# amiga-akab.net
KiCad netlist of a schematic drawn in EAGLE
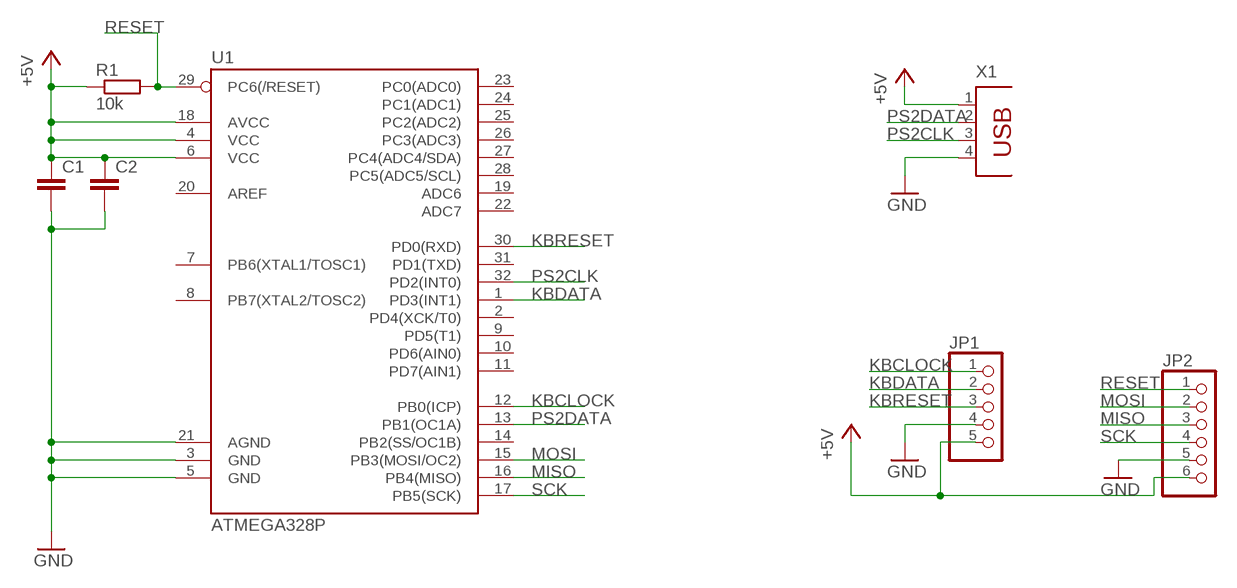
[diagram p0: schematic, sheet 1]

(export (version "E")
  (design (tool "Eeschema 10.0.6"))
  (components
    (comp (ref "C1")
      (value "C-EUC0603")
      (footprint "eagle-import:C0603")
      (libsource (lib "eagle-import") (part "C-EUC0603"))
    )
    (comp (ref "C2")
      (value "C-EUC0603")
      (footprint "eagle-import:C0603")
      (libsource (lib "eagle-import") (part "C-EUC0603"))
    )
    (comp (ref "JP1")
      (value "HEADER-1X5ROUND")
      (footprint "eagle-import:1X05_ROUND")
      (libsource (lib "eagle-import") (part "HEADER-1X5ROUND"))
    )
    (comp (ref "JP2")
      (value "HEADER-1X6ROUND")
      (footprint "eagle-import:1X06_ROUND")
      (libsource (lib "eagle-import") (part "HEADER-1X6ROUND"))
    )
    (comp (ref "R1")
      (value "10k")
      (footprint "eagle-import:R0603")
      (libsource (lib "eagle-import") (part "R-EU_R0603"))
    )
    (comp (ref "U1")
      (value "ATMEGA328P")
      (footprint "eagle-import:TQFP32-08")
      (libsource (lib "eagle-import") (part "ATMEGA328P_TQFP"))
    )
    (comp (ref "X1")
      (value "PN87520")
      (footprint "eagle-import:PN87520")
      (libsource (lib "eagle-import") (part "PN87520"))
    )
  )
  (nets
    (net (code "1") (name "+5V") (class "Default")
      (node (ref "C1") (pin "1") (pinfunction "1_1") (pintype "passive"))
      (node (ref "C2") (pin "1") (pinfunction "1_1") (pintype "passive"))
      (node (ref "JP1") (pin "5") (pinfunction "5_5") (pintype "passive"))
      (node (ref "JP2") (pin "6") (pinfunction "6_6") (pintype "passive"))
      (node (ref "R1") (pin "1") (pinfunction "1_1") (pintype "passive"))
      (node (ref "U1") (pin "18") (pinfunction "AVCC_18") (pintype "bidirectional"))
      (node (ref "U1") (pin "4") (pinfunction "VCC_4") (pintype "bidirectional"))
      (node (ref "U1") (pin "6") (pinfunction "VCC_6") (pintype "bidirectional"))
      (node (ref "X1") (pin "1") (pinfunction "1_1") (pintype "passive"))
    )
    (net (code "2") (name "/KBCLOCK") (class "Default")
      (node (ref "JP1") (pin "1") (pinfunction "1_1") (pintype "passive"))
      (node (ref "U1") (pin "12") (pinfunction "PB0(ICP)_12") (pintype "bidirectional"))
    )
    (net (code "3") (name "/KBDATA") (class "Default")
      (node (ref "JP1") (pin "2") (pinfunction "2_2") (pintype "passive"))
      (node (ref "U1") (pin "1") (pinfunction "PD3(INT1)_1") (pintype "bidirectional"))
    )
    (net (code "4") (name "/KBRESET") (class "Default")
      (node (ref "JP1") (pin "3") (pinfunction "3_3") (pintype "passive"))
      (node (ref "U1") (pin "30") (pinfunction "PD0(RXD)_30") (pintype "bidirectional"))
    )
    (net (code "5") (name "/MISO") (class "Default")
      (node (ref "JP2") (pin "3") (pinfunction "3_3") (pintype "passive"))
      (node (ref "U1") (pin "16") (pinfunction "PB4(MISO)_16") (pintype "bidirectional"))
    )
    (net (code "6") (name "/MOSI") (class "Default")
      (node (ref "JP2") (pin "2") (pinfunction "2_2") (pintype "passive"))
      (node (ref "U1") (pin "15") (pinfunction "PB3(MOSI/OC2)_15") (pintype "bidirectional"))
    )
    (net (code "7") (name "/PS2CLK") (class "Default")
      (node (ref "U1") (pin "32") (pinfunction "PD2(INT0)_32") (pintype "bidirectional"))
      (node (ref "X1") (pin "3") (pinfunction "3_3") (pintype "passive"))
    )
    (net (code "8") (name "/PS2DATA") (class "Default")
      (node (ref "U1") (pin "13") (pinfunction "PB1(OC1A)_13") (pintype "bidirectional"))
      (node (ref "X1") (pin "2") (pinfunction "2_2") (pintype "passive"))
    )
    (net (code "9") (name "/RESET") (class "Default")
      (node (ref "JP2") (pin "1") (pinfunction "1_1") (pintype "passive"))
      (node (ref "R1") (pin "2") (pinfunction "2_2") (pintype "passive"))
      (node (ref "U1") (pin "29") (pinfunction "PC6(/RESET)_29") (pintype "bidirectional"))
    )
    (net (code "10") (name "/SCK") (class "Default")
      (node (ref "JP2") (pin "4") (pinfunction "4_4") (pintype "passive"))
      (node (ref "U1") (pin "17") (pinfunction "PB5(SCK)_17") (pintype "bidirectional"))
    )
    (net (code "11") (name "GND") (class "Default")
      (node (ref "C1") (pin "2") (pinfunction "2_2") (pintype "passive"))
      (node (ref "C2") (pin "2") (pinfunction "2_2") (pintype "passive"))
      (node (ref "JP1") (pin "4") (pinfunction "4_4") (pintype "passive"))
      (node (ref "JP2") (pin "5") (pinfunction "5_5") (pintype "passive"))
      (node (ref "U1") (pin "21") (pinfunction "AGND_21") (pintype "bidirectional"))
      (node (ref "U1") (pin "3") (pinfunction "GND_3") (pintype "bidirectional"))
      (node (ref "U1") (pin "5") (pinfunction "GND_5") (pintype "bidirectional"))
      (node (ref "X1") (pin "4") (pinfunction "4_4") (pintype "passive"))
    )
    (net (code "12") (name "unconnected-(U1-ADC6-Pad19)") (class "Default")
      (node (ref "U1") (pin "19") (pinfunction "ADC6_19") (pintype "bidirectional"))
    )
    (net (code "13") (name "unconnected-(U1-ADC7-Pad22)") (class "Default")
      (node (ref "U1") (pin "22") (pinfunction "ADC7_22") (pintype "bidirectional"))
    )
    (net (code "14") (name "unconnected-(U1-AREF-Pad20)") (class "Default")
      (node (ref "U1") (pin "20") (pinfunction "AREF_20") (pintype "bidirectional"))
    )
    (net (code "15") (name "unconnected-(U1-PB2(SS{slash}OC1B)-Pad14)") (class "Default")
      (node (ref "U1") (pin "14") (pinfunction "PB2(SS/OC1B)_14") (pintype "bidirectional"))
    )
    (net (code "16") (name "unconnected-(U1-PB6(XTAL1{slash}TOSC1)-Pad7)") (class "Default")
      (node (ref "U1") (pin "7") (pinfunction "PB6(XTAL1/TOSC1)_7") (pintype "bidirectional"))
    )
    (net (code "17") (name "unconnected-(U1-PB7(XTAL2{slash}TOSC2)-Pad8)") (class "Default")
      (node (ref "U1") (pin "8") (pinfunction "PB7(XTAL2/TOSC2)_8") (pintype "bidirectional"))
    )
    (net (code "18") (name "unconnected-(U1-PC0(ADC0)-Pad23)") (class "Default")
      (node (ref "U1") (pin "23") (pinfunction "PC0(ADC0)_23") (pintype "bidirectional"))
    )
    (net (code "19") (name "unconnected-(U1-PC1(ADC1)-Pad24)") (class "Default")
      (node (ref "U1") (pin "24") (pinfunction "PC1(ADC1)_24") (pintype "bidirectional"))
    )
    (net (code "20") (name "unconnected-(U1-PC2(ADC2)-Pad25)") (class "Default")
      (node (ref "U1") (pin "25") (pinfunction "PC2(ADC2)_25") (pintype "bidirectional"))
    )
    (net (code "21") (name "unconnected-(U1-PC3(ADC3)-Pad26)") (class "Default")
      (node (ref "U1") (pin "26") (pinfunction "PC3(ADC3)_26") (pintype "bidirectional"))
    )
    (net (code "22") (name "unconnected-(U1-PC4(ADC4{slash}SDA)-Pad27)") (class "Default")
      (node (ref "U1") (pin "27") (pinfunction "PC4(ADC4/SDA)_27") (pintype "bidirectional"))
    )
    (net (code "23") (name "unconnected-(U1-PC5(ADC5{slash}SCL)-Pad28)") (class "Default")
      (node (ref "U1") (pin "28") (pinfunction "PC5(ADC5/SCL)_28") (pintype "bidirectional"))
    )
    (net (code "24") (name "unconnected-(U1-PD1(TXD)-Pad31)") (class "Default")
      (node (ref "U1") (pin "31") (pinfunction "PD1(TXD)_31") (pintype "bidirectional"))
    )
    (net (code "25") (name "unconnected-(U1-PD4(XCK{slash}T0)-Pad2)") (class "Default")
      (node (ref "U1") (pin "2") (pinfunction "PD4(XCK/T0)_2") (pintype "bidirectional"))
    )
    (net (code "26") (name "unconnected-(U1-PD5(T1)-Pad9)") (class "Default")
      (node (ref "U1") (pin "9") (pinfunction "PD5(T1)_9") (pintype "bidirectional"))
    )
    (net (code "27") (name "unconnected-(U1-PD6(AIN0)-Pad10)") (class "Default")
      (node (ref "U1") (pin "10") (pinfunction "PD6(AIN0)_10") (pintype "bidirectional"))
    )
    (net (code "28") (name "unconnected-(U1-PD7(AIN1)-Pad11)") (class "Default")
      (node (ref "U1") (pin "11") (pinfunction "PD7(AIN1)_11") (pintype "bidirectional"))
    )
  )
)
